# sch.net
KiCad netlist of a schematic drawn in EasyEDA
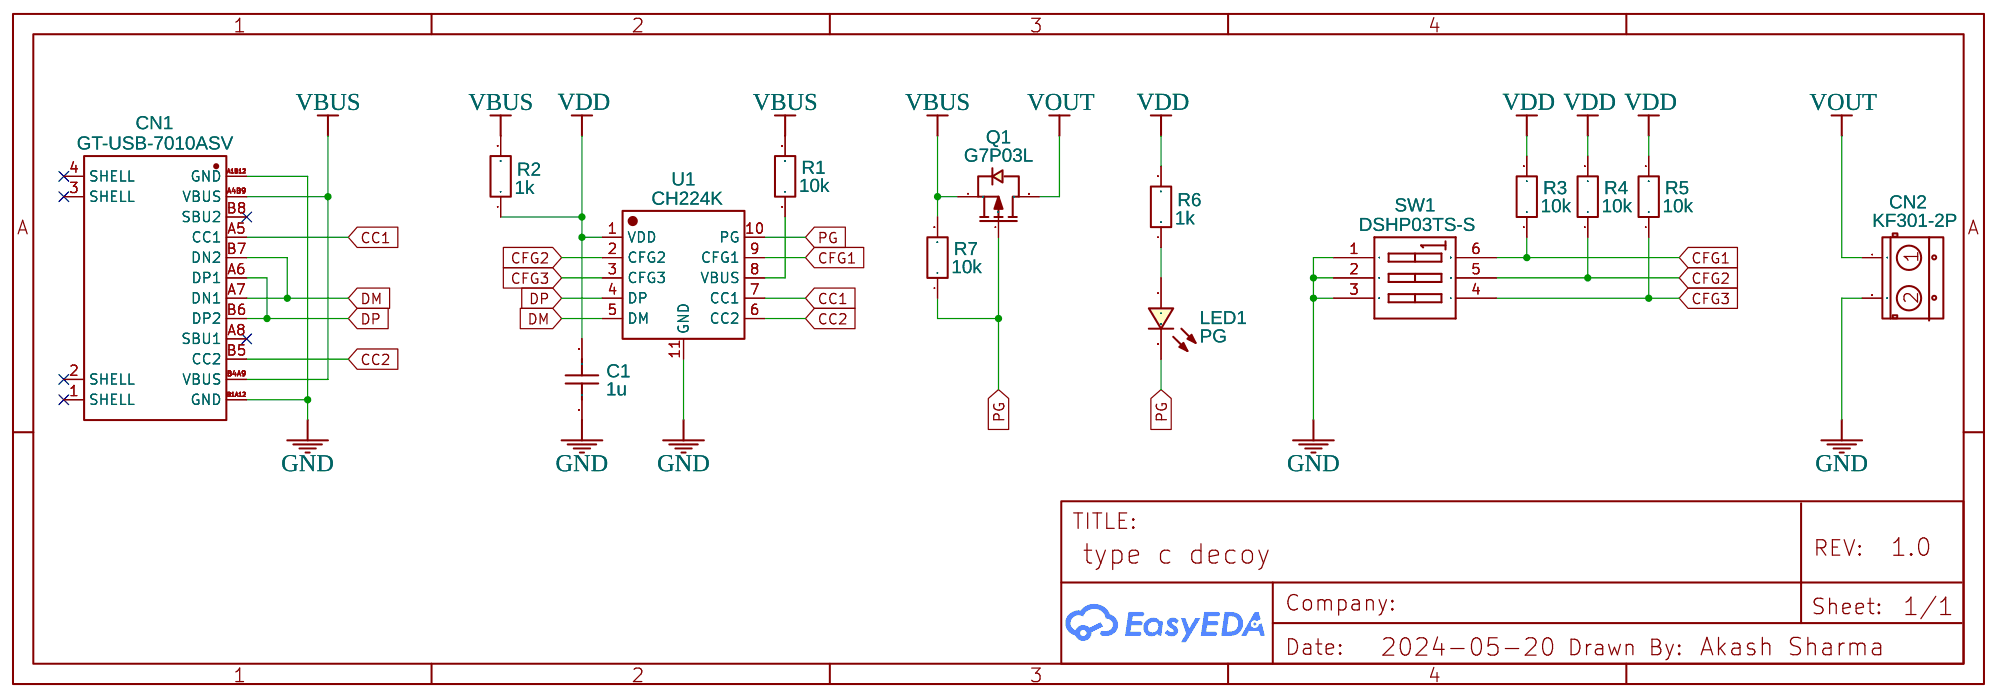
[diagram p0: schematic sheet]

(export (version "E")
  (design (tool "Eeschema 10.0.6"))
  (components
    (comp (ref "C1")
      (value "1u")
      (fields (field (name "Manufacturer Part") "CL10A105KB8NNNC") (field (name "Manufacturer") "SAMSUNG"))
      (libsource (lib "") (part "CC0603KRX7R9BB104"))
    )
    (comp (ref "CN1")
      (value "GT-USB-7010ASV")
      (fields (field (name "Manufacturer") "G-Switch(品赞)"))
      (libsource (lib "") (part "GT-USB-7010ASV"))
    )
    (comp (ref "CN2")
      (value "KF301-2P")
      (fields
        (field (name "Manufacturer Part") "KF301-5.0-2P")
        (field (name "Manufacturer") "Cixi Kefa Elec")
      )
      (libsource (lib "") (part "Unknown_920_-225"))
    )
    (comp (ref "LED1")
      (value "PG")
      (fields
        (field (name "Manufacturer Part") "19-217/GHC-YR1S2/3T")
        (field (name "Manufacturer") "EVERLIGHT")
      )
      (libsource (lib "") (part "LED-0603-GREEN"))
    )
    (comp (ref "Q1")
      (value "G7P03L")
      (fields (field (name "Manufacturer") "GOFORD"))
      (libsource (lib "") (part "G7P03L"))
    )
    (comp (ref "R1")
      (value "10k")
      (fields (field (name "Manufacturer Part") "0603WAF1002T5E") (field (name "Manufacturer") "UniOhm"))
      (libsource (lib "") (part "Res_0603(1/10W)_EU"))
    )
    (comp (ref "R2")
      (value "1k")
      (fields (field (name "Manufacturer Part") "0603WAF1001T5E") (field (name "Manufacturer") "UniOhm"))
      (libsource (lib "") (part "Res_0603(1/10W)_EU"))
    )
    (comp (ref "R3")
      (value "10k")
      (fields (field (name "Manufacturer Part") "0603WAF1002T5E") (field (name "Manufacturer") "UniOhm"))
      (libsource (lib "") (part "Res_0603(1/10W)_EU"))
    )
    (comp (ref "R4")
      (value "10k")
      (fields (field (name "Manufacturer Part") "0603WAF1002T5E") (field (name "Manufacturer") "UniOhm"))
      (libsource (lib "") (part "Res_0603(1/10W)_EU"))
    )
    (comp (ref "R5")
      (value "10k")
      (fields (field (name "Manufacturer Part") "0603WAF1002T5E") (field (name "Manufacturer") "UniOhm"))
      (libsource (lib "") (part "Res_0603(1/10W)_EU"))
    )
    (comp (ref "R6")
      (value "1k")
      (fields (field (name "Manufacturer Part") "0603WAF1001T5E") (field (name "Manufacturer") "UniOhm"))
      (libsource (lib "") (part "Res_0603(1/10W)_EU"))
    )
    (comp (ref "R7")
      (value "10k")
      (fields (field (name "Manufacturer Part") "0603WAF1002T5E") (field (name "Manufacturer") "UniOhm"))
      (libsource (lib "") (part "Res_0603(1/10W)_EU"))
    )
    (comp (ref "SW1")
      (value "DSHP03TS-S")
      (fields (field (name "Manufacturer") "XKB Enterprise"))
      (libsource (lib "") (part "DSHP03TS-S"))
    )
    (comp (ref "U1")
      (value "CH224K")
      (fields (field (name "Manufacturer") "WCH"))
      (libsource (lib "") (part "CH224K"))
    )
  )
  (nets
    (net (code "1") (name "CC1") (class "Default")
      (node (ref "CN1") (pin "A5") (pinfunction "CC1_A5") (pintype "unspecified"))
      (node (ref "U1") (pin "7") (pinfunction "CC1_7") (pintype "unspecified"))
    )
    (net (code "2") (name "CC2") (class "Default")
      (node (ref "CN1") (pin "B5") (pinfunction "CC2_B5") (pintype "unspecified"))
      (node (ref "U1") (pin "6") (pinfunction "CC2_6") (pintype "unspecified"))
    )
    (net (code "3") (name "CFG1") (class "Default")
      (node (ref "R3") (pin "1") (pinfunction "1_1") (pintype "unspecified"))
      (node (ref "SW1") (pin "6") (pinfunction "6_6") (pintype "input"))
      (node (ref "U1") (pin "9") (pinfunction "CFG1_9") (pintype "unspecified"))
    )
    (net (code "4") (name "CFG2") (class "Default")
      (node (ref "R4") (pin "1") (pinfunction "1_1") (pintype "unspecified"))
      (node (ref "SW1") (pin "5") (pinfunction "5_5") (pintype "input"))
      (node (ref "U1") (pin "2") (pinfunction "CFG2_2") (pintype "unspecified"))
    )
    (net (code "5") (name "CFG3") (class "Default")
      (node (ref "R5") (pin "1") (pinfunction "1_1") (pintype "unspecified"))
      (node (ref "SW1") (pin "4") (pinfunction "4_4") (pintype "input"))
      (node (ref "U1") (pin "3") (pinfunction "CFG3_3") (pintype "unspecified"))
    )
    (net (code "6") (name "DM") (class "Default")
      (node (ref "CN1") (pin "A7") (pinfunction "DN1_A7") (pintype "unspecified"))
      (node (ref "CN1") (pin "B7") (pinfunction "DN2_B7") (pintype "unspecified"))
      (node (ref "U1") (pin "5") (pinfunction "DM_5") (pintype "unspecified"))
    )
    (net (code "7") (name "DP") (class "Default")
      (node (ref "CN1") (pin "A6") (pinfunction "DP1_A6") (pintype "unspecified"))
      (node (ref "CN1") (pin "B6") (pinfunction "DP2_B6") (pintype "unspecified"))
      (node (ref "U1") (pin "4") (pinfunction "DP_4") (pintype "unspecified"))
    )
    (net (code "8") (name "GND") (class "Default")
      (node (ref "C1") (pin "1") (pinfunction "1_1") (pintype "unspecified"))
      (node (ref "CN1") (pin "A1B12") (pinfunction "GND_A1B12") (pintype "unspecified"))
      (node (ref "CN1") (pin "B1A12") (pinfunction "GND_B1A12") (pintype "unspecified"))
      (node (ref "CN2") (pin "2") (pinfunction "2_2") (pintype "unspecified"))
      (node (ref "SW1") (pin "1") (pinfunction "1_1") (pintype "input"))
      (node (ref "SW1") (pin "2") (pinfunction "2_2") (pintype "input"))
      (node (ref "SW1") (pin "3") (pinfunction "3_3") (pintype "input"))
      (node (ref "U1") (pin "11") (pinfunction "GND_11") (pintype "unspecified"))
    )
    (net (code "9") (name "Net-(LED1-A)") (class "Default")
      (node (ref "LED1") (pin "1") (pinfunction "A_1") (pintype "input"))
      (node (ref "R6") (pin "1") (pinfunction "1_1") (pintype "unspecified"))
    )
    (net (code "10") (name "Net-(U1-VBUS)") (class "Default")
      (node (ref "R1") (pin "1") (pinfunction "1_1") (pintype "unspecified"))
      (node (ref "U1") (pin "8") (pinfunction "VBUS_8") (pintype "unspecified"))
    )
    (net (code "11") (name "PG") (class "Default")
      (node (ref "LED1") (pin "2") (pinfunction "C_2") (pintype "input"))
      (node (ref "Q1") (pin "1") (pinfunction "G_1") (pintype "unspecified"))
      (node (ref "R7") (pin "1") (pinfunction "1_1") (pintype "unspecified"))
      (node (ref "U1") (pin "10") (pinfunction "PG_10") (pintype "unspecified"))
    )
    (net (code "12") (name "VBUS") (class "Default")
      (node (ref "CN1") (pin "A4B9") (pinfunction "VBUS_A4B9") (pintype "unspecified"))
      (node (ref "CN1") (pin "B4A9") (pinfunction "VBUS_B4A9") (pintype "unspecified"))
      (node (ref "Q1") (pin "2") (pinfunction "S_2") (pintype "unspecified"))
      (node (ref "R1") (pin "2") (pinfunction "2_2") (pintype "unspecified"))
      (node (ref "R2") (pin "2") (pinfunction "2_2") (pintype "unspecified"))
      (node (ref "R7") (pin "2") (pinfunction "2_2") (pintype "unspecified"))
    )
    (net (code "13") (name "VDD") (class "Default")
      (node (ref "C1") (pin "2") (pinfunction "2_2") (pintype "unspecified"))
      (node (ref "R2") (pin "1") (pinfunction "1_1") (pintype "unspecified"))
      (node (ref "R3") (pin "2") (pinfunction "2_2") (pintype "unspecified"))
      (node (ref "R4") (pin "2") (pinfunction "2_2") (pintype "unspecified"))
      (node (ref "R5") (pin "2") (pinfunction "2_2") (pintype "unspecified"))
      (node (ref "R6") (pin "2") (pinfunction "2_2") (pintype "unspecified"))
      (node (ref "U1") (pin "1") (pinfunction "VDD_1") (pintype "unspecified"))
    )
    (net (code "14") (name "VOUT") (class "Default")
      (node (ref "CN2") (pin "1") (pinfunction "1_1") (pintype "unspecified"))
      (node (ref "Q1") (pin "3") (pinfunction "D_3") (pintype "unspecified"))
    )
    (net (code "15") (name "unconnected-(CN1-SBU1-PadA8)") (class "Default")
      (node (ref "CN1") (pin "A8") (pinfunction "SBU1_A8") (pintype "unspecified+no_connect"))
    )
    (net (code "16") (name "unconnected-(CN1-SBU2-PadB8)") (class "Default")
      (node (ref "CN1") (pin "B8") (pinfunction "SBU2_B8") (pintype "unspecified+no_connect"))
    )
    (net (code "17") (name "unconnected-(CN1-SHELL-Pad1)") (class "Default")
      (node (ref "CN1") (pin "1") (pinfunction "SHELL_1") (pintype "unspecified+no_connect"))
    )
    (net (code "18") (name "unconnected-(CN1-SHELL-Pad2)") (class "Default")
      (node (ref "CN1") (pin "2") (pinfunction "SHELL_2") (pintype "unspecified+no_connect"))
    )
    (net (code "19") (name "unconnected-(CN1-SHELL-Pad3)") (class "Default")
      (node (ref "CN1") (pin "3") (pinfunction "SHELL_3") (pintype "unspecified+no_connect"))
    )
    (net (code "20") (name "unconnected-(CN1-SHELL-Pad4)") (class "Default")
      (node (ref "CN1") (pin "4") (pinfunction "SHELL_4") (pintype "unspecified+no_connect"))
    )
  )
)
